# elec_array.net
KiCad netlist of a schematic drawn in Altium Designer
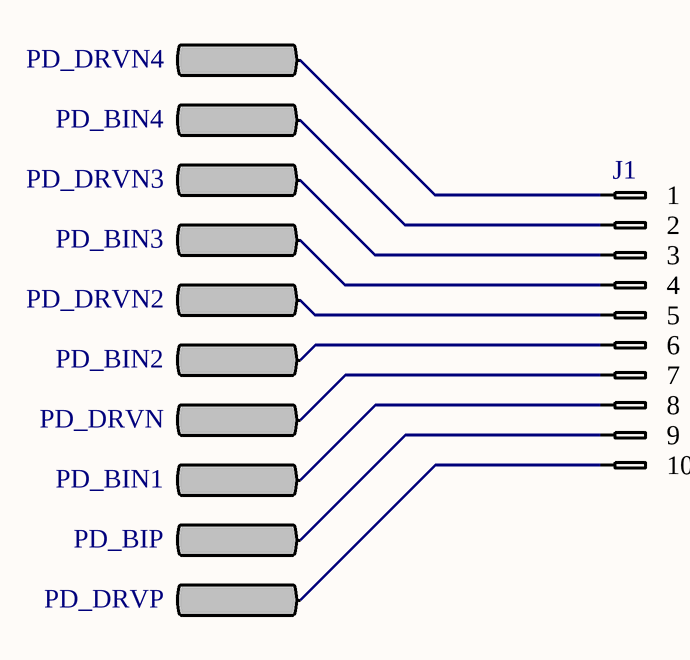
[diagram p0: elec_array.SchDoc]

(export (version "E")
  (design (tool "Eeschema 10.0.6"))
  (components
    (comp (ref "J1")
      (value "Array_Conn_Mate_Pad")
      (footprint "ARRAY_CONN_MATE_PAD")
      (libsource (lib "elec_array") (part "Array_Conn_Mate_Pad"))
    )
    (comp (ref "PD_BIN1")
      (value "Skin_Interface_Pad")
      (footprint "Skin_Interface_Pad")
      (libsource (lib "elec_array") (part "Skin_Interface_Pad"))
    )
    (comp (ref "PD_BIN2")
      (value "Skin_Interface_Pad")
      (footprint "Skin_Interface_Pad")
      (libsource (lib "elec_array") (part "Skin_Interface_Pad"))
    )
    (comp (ref "PD_BIN3")
      (value "Skin_Interface_Pad")
      (footprint "Skin_Interface_Pad")
      (libsource (lib "elec_array") (part "Skin_Interface_Pad"))
    )
    (comp (ref "PD_BIN4")
      (value "Skin_Interface_Pad")
      (footprint "Skin_Interface_Pad")
      (libsource (lib "elec_array") (part "Skin_Interface_Pad"))
    )
    (comp (ref "PD_BIP")
      (value "Skin_Interface_Pad")
      (footprint "Skin_Interface_Pad")
      (libsource (lib "elec_array") (part "Skin_Interface_Pad"))
    )
    (comp (ref "PD_DRVN")
      (value "Skin_Interface_Pad")
      (footprint "Skin_Interface_Pad")
      (libsource (lib "elec_array") (part "Skin_Interface_Pad"))
    )
    (comp (ref "PD_DRVN2")
      (value "Skin_Interface_Pad")
      (footprint "Skin_Interface_Pad")
      (libsource (lib "elec_array") (part "Skin_Interface_Pad"))
    )
    (comp (ref "PD_DRVN3")
      (value "Skin_Interface_Pad")
      (footprint "Skin_Interface_Pad")
      (libsource (lib "elec_array") (part "Skin_Interface_Pad"))
    )
    (comp (ref "PD_DRVN4")
      (value "Skin_Interface_Pad")
      (footprint "Skin_Interface_Pad")
      (libsource (lib "elec_array") (part "Skin_Interface_Pad"))
    )
    (comp (ref "PD_DRVP")
      (value "Skin_Interface_Pad")
      (footprint "Skin_Interface_Pad")
      (libsource (lib "elec_array") (part "Skin_Interface_Pad"))
    )
  )
  (nets
    (net (code "1") (name "Net-(J1-Pad1)") (class "Default")
      (node (ref "J1") (pin "1") (pinfunction "1_1") (pintype "passive"))
      (node (ref "PD_DRVN4") (pin "1") (pinfunction "1_1") (pintype "passive"))
    )
    (net (code "2") (name "Net-(J1-Pad2)") (class "Default")
      (node (ref "J1") (pin "2") (pinfunction "2_2") (pintype "passive"))
      (node (ref "PD_BIN4") (pin "1") (pinfunction "1_1") (pintype "passive"))
    )
    (net (code "3") (name "Net-(J1-Pad3)") (class "Default")
      (node (ref "J1") (pin "3") (pinfunction "3_3") (pintype "passive"))
      (node (ref "PD_DRVN3") (pin "1") (pinfunction "1_1") (pintype "passive"))
    )
    (net (code "4") (name "Net-(J1-Pad4)") (class "Default")
      (node (ref "J1") (pin "4") (pinfunction "4_4") (pintype "passive"))
      (node (ref "PD_BIN3") (pin "1") (pinfunction "1_1") (pintype "passive"))
    )
    (net (code "5") (name "Net-(J1-Pad5)") (class "Default")
      (node (ref "J1") (pin "5") (pinfunction "5_5") (pintype "passive"))
      (node (ref "PD_DRVN2") (pin "1") (pinfunction "1_1") (pintype "passive"))
    )
    (net (code "6") (name "Net-(J1-Pad6)") (class "Default")
      (node (ref "J1") (pin "6") (pinfunction "6_6") (pintype "passive"))
      (node (ref "PD_BIN2") (pin "1") (pinfunction "1_1") (pintype "passive"))
    )
    (net (code "7") (name "Net-(J1-Pad7)") (class "Default")
      (node (ref "J1") (pin "7") (pinfunction "7_7") (pintype "passive"))
      (node (ref "PD_DRVN") (pin "1") (pinfunction "1_1") (pintype "passive"))
    )
    (net (code "8") (name "Net-(J1-Pad8)") (class "Default")
      (node (ref "J1") (pin "8") (pinfunction "8_8") (pintype "passive"))
      (node (ref "PD_BIN1") (pin "1") (pinfunction "1_1") (pintype "passive"))
    )
    (net (code "9") (name "Net-(J1-Pad9)") (class "Default")
      (node (ref "J1") (pin "9") (pinfunction "9_9") (pintype "passive"))
      (node (ref "PD_BIP") (pin "1") (pinfunction "1_1") (pintype "passive"))
    )
    (net (code "10") (name "Net-(J1-Pad10)") (class "Default")
      (node (ref "J1") (pin "10") (pinfunction "10_10") (pintype "passive"))
      (node (ref "PD_DRVP") (pin "1") (pinfunction "1_1") (pintype "passive"))
    )
  )
)
